# Power.net
KiCad netlist of a schematic drawn in Altium Designer
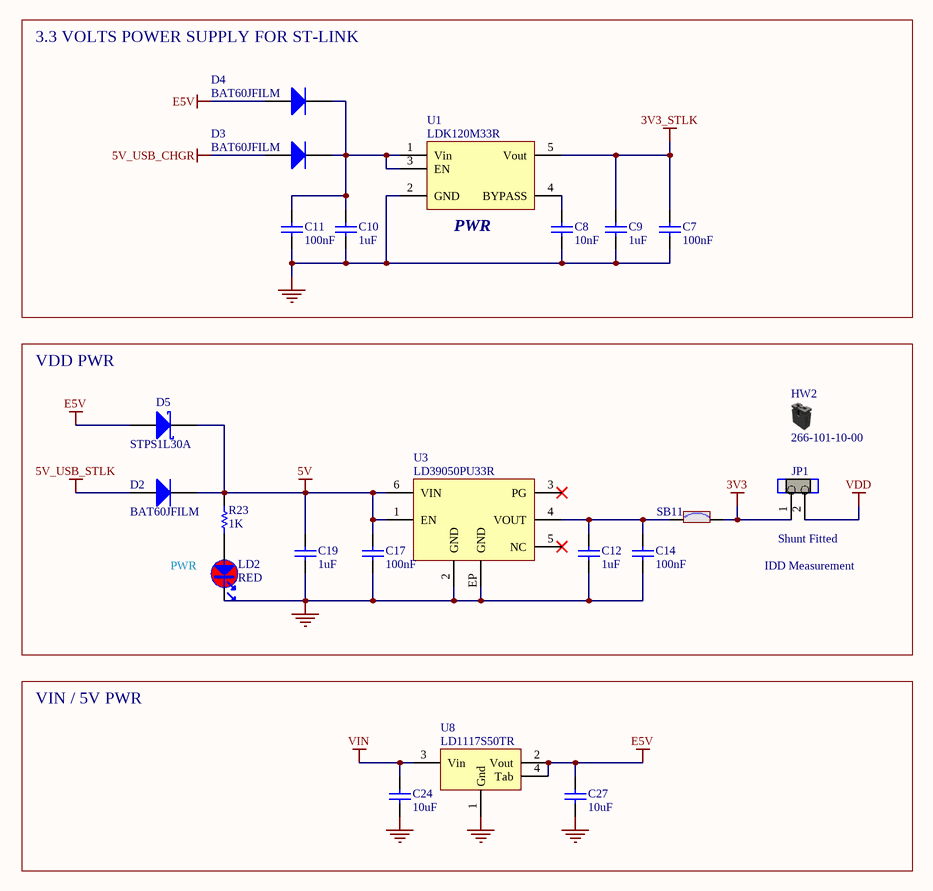
[diagram p0: Power.SchDoc]

(export (version "E")
  (design (tool "Eeschema 10.0.6"))
  (components
    (comp (ref "C7")
      (value "100nF")
      (footprint "C0402")
      (description "Capacitor, MLCC, 100nF, 16V, X7R, 10%, 0402, T=0,5mm")
      (fields
        (field (name "INTERNAL_PART_NUMBER") "MCD-00102")
        (field (name "MANUFACTURER_PART_NUMBER") "CC0402KRX7R7BB104")
        (field (name "PROVIDED_BY") "SUBCO")
      )
      (libsource (lib "MCD_PARTS_database") (part "Capacitor"))
    )
    (comp (ref "C8")
      (value "10nF")
      (footprint "C0402")
      (description "Capacitor, MLCC, 10nF, 16V, X7R, 10%, 0402, T=0.5mm")
      (fields
        (field (name "INTERNAL_PART_NUMBER") "MCD-00011")
        (field (name "MANUFACTURER_PART_NUMBER") "CC0402KRX7R7BB103")
        (field (name "PROVIDED_BY") "SUBCO")
      )
      (libsource (lib "MCD_PARTS_database") (part "Capacitor"))
    )
    (comp (ref "C9")
      (value "1uF")
      (footprint "C0402")
      (description "Capacitor, MLCC, 1uF, 6V3, X5R, 10%, 0402, T=0,5mm")
      (fields
        (field (name "INTERNAL_PART_NUMBER") "MCD-00095")
        (field (name "MANUFACTURER_PART_NUMBER") "GRM155R61E105KA12")
        (field (name "PROVIDED_BY") "SUBCO")
      )
      (libsource (lib "MCD_PARTS_database") (part "Capacitor"))
    )
    (comp (ref "C10")
      (value "1uF")
      (footprint "C0402")
      (description "Capacitor, MLCC, 1uF, 6V3, X5R, 10%, 0402, T=0,5mm")
      (fields
        (field (name "INTERNAL_PART_NUMBER") "MCD-00095")
        (field (name "MANUFACTURER_PART_NUMBER") "GRM155R61E105KA12")
        (field (name "PROVIDED_BY") "SUBCO")
      )
      (libsource (lib "MCD_PARTS_database") (part "Capacitor"))
    )
    (comp (ref "C11")
      (value "100nF")
      (footprint "C0402")
      (description "Capacitor, MLCC, 100nF, 16V, X7R, 10%, 0402, T=0,5mm")
      (fields
        (field (name "INTERNAL_PART_NUMBER") "MCD-00102")
        (field (name "MANUFACTURER_PART_NUMBER") "CC0402KRX7R7BB104")
        (field (name "PROVIDED_BY") "SUBCO")
      )
      (libsource (lib "MCD_PARTS_database") (part "Capacitor"))
    )
    (comp (ref "C12")
      (value "1uF")
      (footprint "C0402")
      (description "Capacitor, MLCC, 1uF, 6V3, X5R, 10%, 0402, T=0,5mm")
      (fields
        (field (name "INTERNAL_PART_NUMBER") "MCD-00095")
        (field (name "MANUFACTURER_PART_NUMBER") "GRM155R61E105KA12")
        (field (name "PROVIDED_BY") "SUBCO")
      )
      (libsource (lib "MCD_PARTS_database") (part "Capacitor"))
    )
    (comp (ref "C14")
      (value "100nF")
      (footprint "C0402")
      (description "Capacitor, MLCC, 100nF, 16V, X7R, 10%, 0402, T=0,5mm")
      (fields
        (field (name "INTERNAL_PART_NUMBER") "MCD-00102")
        (field (name "MANUFACTURER_PART_NUMBER") "CC0402KRX7R7BB104")
        (field (name "PROVIDED_BY") "SUBCO")
      )
      (libsource (lib "MCD_PARTS_database") (part "Capacitor"))
    )
    (comp (ref "C17")
      (value "100nF")
      (footprint "C0402")
      (description "Capacitor, MLCC, 100nF, 16V, X7R, 10%, 0402, T=0,5mm")
      (fields
        (field (name "INTERNAL_PART_NUMBER") "MCD-00102")
        (field (name "MANUFACTURER_PART_NUMBER") "CC0402KRX7R7BB104")
        (field (name "PROVIDED_BY") "SUBCO")
      )
      (libsource (lib "MCD_PARTS_database") (part "Capacitor"))
    )
    (comp (ref "C19")
      (value "1uF")
      (footprint "C0402")
      (description "Capacitor, MLCC, 1uF, 6V3, X5R, 10%, 0402, T=0,5mm")
      (fields
        (field (name "INTERNAL_PART_NUMBER") "MCD-00095")
        (field (name "MANUFACTURER_PART_NUMBER") "GRM155R61E105KA12")
        (field (name "PROVIDED_BY") "SUBCO")
      )
      (libsource (lib "MCD_PARTS_database") (part "Capacitor"))
    )
    (comp (ref "C24")
      (value "10uF")
      (footprint "C0805")
      (description "Capacitor, MLCC, 10uF, 25V, X5R, 10%, 0805, T=0,85mm")
      (fields
        (field (name "INTERNAL_PART_NUMBER") "MCD-00014")
        (field (name "MANUFACTURER_PART_NUMBER") "CC0805KRX5R8BB106")
        (field (name "PROVIDED_BY") "SUBCO")
      )
      (libsource (lib "MCD_PARTS_database") (part "Capacitor"))
    )
    (comp (ref "C27")
      (value "10uF")
      (footprint "C0805")
      (description "Capacitor, MLCC, 10uF, 25V, X5R, 10%, 0805, T=0,85mm")
      (fields
        (field (name "INTERNAL_PART_NUMBER") "MCD-00014")
        (field (name "MANUFACTURER_PART_NUMBER") "CC0805KRX5R8BB106")
        (field (name "PROVIDED_BY") "SUBCO")
      )
      (libsource (lib "MCD_PARTS_database") (part "Capacitor"))
    )
    (comp (ref "D2")
      (value "BAT60JFILM")
      (footprint "DIO_SOD323")
      (fields
        (field (name "INTERNAL_PART_NUMBER") "MCD-00034")
        (field (name "MANUFACTURER") "STMICROELECTRONICS")
        (field (name "BMS_PART_NUMBER") "9151097")
        (field (name "PROVIDED_BY") "SUBCO with ST control")
      )
      (libsource (lib "MCD_PARTS_database") (part "BAT60JFILM"))
    )
    (comp (ref "D3")
      (value "BAT60JFILM")
      (footprint "DIO_SOD323")
      (fields
        (field (name "INTERNAL_PART_NUMBER") "MCD-00034")
        (field (name "MANUFACTURER") "STMICROELECTRONICS")
        (field (name "BMS_PART_NUMBER") "9151097")
        (field (name "PROVIDED_BY") "SUBCO with ST control")
      )
      (libsource (lib "MCD_PARTS_database") (part "BAT60JFILM"))
    )
    (comp (ref "D4")
      (value "BAT60JFILM")
      (footprint "DIO_SOD323")
      (fields
        (field (name "INTERNAL_PART_NUMBER") "MCD-00034")
        (field (name "MANUFACTURER") "STMICROELECTRONICS")
        (field (name "BMS_PART_NUMBER") "9151097")
        (field (name "PROVIDED_BY") "SUBCO with ST control")
      )
      (libsource (lib "MCD_PARTS_database") (part "BAT60JFILM"))
    )
    (comp (ref "D5")
      (value "STPS1L30A")
      (footprint "DIO_SMA_1A_2K")
      (description "LOW DROP POWER SCHOTTKY RECTIFIER 1A 30V VF=0.3V")
      (fields
        (field (name "INTERNAL_PART_NUMBER") "MCD-01059")
        (field (name "MANUFACTURER") "STMICROELECTRONICS")
        (field (name "PROVIDED_BY") "SUBCO with ST control")
      )
      (libsource (lib "MCD_PARTS_database") (part "STPS1L40M"))
    )
    (comp (ref "HW2")
      (value "266-101-10-00")
      (description "SHUNT 1.27mm BLACK")
      (fields
        (field (name "INTERNAL_PART_NUMBER") "MCD-01409")
        (field (name "MANUFACTURER") "W & P Products")
        (field (name "PROVIDED_BY") "SUBCO")
      )
      (libsource (lib "MCD_PARTS_database") (part "Shunt Black 1.27mm 266-101-10-00"))
    )
    (comp (ref "JP1")
      (value "Shunt Fitted")
      (footprint "CON_WP_707-2-02-2-20-00")
      (description "Header, 2x1, 1,27mm, Right Angled, Single Row, Height 3.05mm/1.27mm")
      (fields
        (field (name "INTERNAL_PART_NUMBER") "MCD-01428")
        (field (name "MANUFACTURER_PART_NUMBER") "707-2-02-2-20-00")
        (field (name "PROVIDED_BY") "SUBCO")
      )
      (libsource (lib "MCD_PARTS_database") (part "Jumper_Header1.27 2x1 Fitted"))
    )
    (comp (ref "LD2")
      (value "RED")
      (footprint "LED_0603_RED_H0P4")
      (description "LED, Red, 0603")
      (fields
        (field (name "INTERNAL_PART_NUMBER") "MCD-00322")
        (field (name "MANUFACTURER_PART_NUMBER") "19-217/R6C-AL1M2VY/3T")
        (field (name "PROVIDED_BY") "SUBCO")
      )
      (libsource (lib "MCD_PARTS_database") (part "LED_red"))
    )
    (comp (ref "R23")
      (value "1K")
      (footprint "R0402")
      (description "Resistor,1K,0402,1%,1/16W")
      (fields
        (field (name "INTERNAL_PART_NUMBER") "MCD-00061")
        (field (name "MANUFACTURER_PART_NUMBER") "RC0402FR-071KL")
        (field (name "PROVIDED_BY") "SUBCO")
      )
      (libsource (lib "MCD_PARTS_database") (part "Resistor"))
    )
    (comp (ref "SB11")
      (value "SB_ON")
      (footprint "SOLDER-BRIDGE_R0603-0R")
      (description "Solder Bridge ON")
      (fields
        (field (name "INTERNAL_PART_NUMBER") "MCD-00071")
        (field (name "MANUFACTURER_PART_NUMBER") "RC0603JR-070RL")
        (field (name "PROVIDED_BY") "SUBCO")
      )
      (libsource (lib "MCD_PARTS_database") (part "SB_ON"))
    )
    (comp (ref "U1")
      (value "LDK120M33R")
      (footprint "REG_SOT23-5L")
      (description "200 mA low quiescent current very low noise LDO")
      (fields
        (field (name "INTERNAL_PART_NUMBER") "MCD-00663")
        (field (name "MANUFACTURER") "STMICROELECTRONICS")
        (field (name "PROVIDED_BY") "SUBCO with ST control")
      )
      (libsource (lib "MCD_PARTS_database") (part "LDK120M33R"))
    )
    (comp (ref "U3")
      (value "LD39050PU33R")
      (footprint "ICC_DFN6-EPAD_3X3_P095")
      (description "Low quiescent current and low noise voltage regulators")
      (fields
        (field (name "INTERNAL_PART_NUMBER") "MCD-00215")
        (field (name "MANUFACTURER") "STMICROELECTRONICS")
        (field (name "PROVIDED_BY") "SUBCO with ST control")
      )
      (libsource (lib "MCD_PARTS_database") (part "LD39050PU33R"))
    )
    (comp (ref "U8")
      (value "LD1117S50TR")
      (footprint "REG_SOT223-TAB")
      (description "IC REG LDO 5V 0.8A SOT223")
      (fields
        (field (name "INTERNAL_PART_NUMBER") "MCD-00088")
        (field (name "MANUFACTURER") "STMICROELECTRONICS")
        (field (name "PROVIDED_BY") "SUBCO with ST control")
      )
      (libsource (lib "MCD_PARTS_database") (part "LD1117S50TR"))
    )
  )
  (nets
    (net (code "1") (name "3V3") (class "Default")
      (node (ref "JP1") (pin "1") (pinfunction "1_1") (pintype "passive"))
      (node (ref "SB11") (pin "2") (pinfunction "2_2") (pintype "passive"))
    )
    (net (code "2") (name "3V3_STLK") (class "Default")
      (node (ref "C7") (pin "2") (pinfunction "2_2") (pintype "passive"))
      (node (ref "C9") (pin "2") (pinfunction "2_2") (pintype "passive"))
      (node (ref "U1") (pin "5") (pinfunction "Vout_5") (pintype "power_in"))
    )
    (net (code "3") (name "5V") (class "Default")
      (node (ref "C17") (pin "2") (pinfunction "2_2") (pintype "passive"))
      (node (ref "C19") (pin "2") (pinfunction "2_2") (pintype "passive"))
      (node (ref "D2") (pin "2") (pinfunction "K_2") (pintype "passive"))
      (node (ref "D5") (pin "2") (pinfunction "K_2") (pintype "passive"))
      (node (ref "R23") (pin "2") (pinfunction "2_2") (pintype "passive"))
      (node (ref "U3") (pin "1") (pinfunction "EN_1") (pintype "passive"))
      (node (ref "U3") (pin "6") (pinfunction "VIN_6") (pintype "passive"))
    )
    (net (code "4") (name "5V_USB_CHGR") (class "Default")
      (node (ref "D3") (pin "1") (pinfunction "A_1") (pintype "passive"))
    )
    (net (code "5") (name "5V_USB_STLK") (class "Default")
      (node (ref "D2") (pin "1") (pinfunction "A_1") (pintype "passive"))
    )
    (net (code "6") (name "E5V") (class "Default")
      (node (ref "C27") (pin "2") (pinfunction "2_2") (pintype "passive"))
      (node (ref "D4") (pin "1") (pinfunction "A_1") (pintype "passive"))
      (node (ref "D5") (pin "1") (pinfunction "A_1") (pintype "passive"))
      (node (ref "U8") (pin "2") (pinfunction "Vout_2") (pintype "passive"))
      (node (ref "U8") (pin "4") (pinfunction "Tab_4") (pintype "passive"))
    )
    (net (code "7") (name "GND") (class "Default")
      (node (ref "C10") (pin "1") (pinfunction "1_1") (pintype "passive"))
      (node (ref "C11") (pin "1") (pinfunction "1_1") (pintype "passive"))
      (node (ref "C12") (pin "1") (pinfunction "1_1") (pintype "passive"))
      (node (ref "C14") (pin "1") (pinfunction "1_1") (pintype "passive"))
      (node (ref "C17") (pin "1") (pinfunction "1_1") (pintype "passive"))
      (node (ref "C19") (pin "1") (pinfunction "1_1") (pintype "passive"))
      (node (ref "C24") (pin "1") (pinfunction "1_1") (pintype "passive"))
      (node (ref "C27") (pin "1") (pinfunction "1_1") (pintype "passive"))
      (node (ref "C7") (pin "1") (pinfunction "1_1") (pintype "passive"))
      (node (ref "C8") (pin "1") (pinfunction "1_1") (pintype "passive"))
      (node (ref "C9") (pin "1") (pinfunction "1_1") (pintype "passive"))
      (node (ref "LD2") (pin "2") (pintype "passive"))
      (node (ref "U1") (pin "2") (pinfunction "GND_2") (pintype "passive"))
      (node (ref "U3") (pin "2") (pinfunction "GND_2") (pintype "passive"))
      (node (ref "U3") (pin "EP") (pinfunction "GND_EP") (pintype "passive"))
      (node (ref "U8") (pin "1") (pinfunction "Gnd_1") (pintype "passive"))
    )
    (net (code "8") (name "Net-(D3-K)") (class "Default")
      (node (ref "C10") (pin "2") (pinfunction "2_2") (pintype "passive"))
      (node (ref "C11") (pin "2") (pinfunction "2_2") (pintype "passive"))
      (node (ref "D3") (pin "2") (pinfunction "K_2") (pintype "passive"))
      (node (ref "D4") (pin "2") (pinfunction "K_2") (pintype "passive"))
      (node (ref "U1") (pin "1") (pinfunction "Vin_1") (pintype "power_in"))
      (node (ref "U1") (pin "3") (pinfunction "EN_3") (pintype "passive"))
    )
    (net (code "9") (name "Net-(LD2-Pad1)") (class "Default")
      (node (ref "LD2") (pin "1") (pintype "passive"))
      (node (ref "R23") (pin "1") (pinfunction "1_1") (pintype "passive"))
    )
    (net (code "10") (name "Net-(U1-BYPASS)") (class "Default")
      (node (ref "C8") (pin "2") (pinfunction "2_2") (pintype "passive"))
      (node (ref "U1") (pin "4") (pinfunction "BYPASS_4") (pintype "passive"))
    )
    (net (code "11") (name "Net-(U3-VOUT)") (class "Default")
      (node (ref "C12") (pin "2") (pinfunction "2_2") (pintype "passive"))
      (node (ref "C14") (pin "2") (pinfunction "2_2") (pintype "passive"))
      (node (ref "SB11") (pin "1") (pinfunction "1_1") (pintype "passive"))
      (node (ref "U3") (pin "4") (pinfunction "VOUT_4") (pintype "passive"))
    )
    (net (code "12") (name "VDD") (class "Default")
      (node (ref "JP1") (pin "2") (pinfunction "2_2") (pintype "passive"))
    )
    (net (code "13") (name "VIN") (class "Default")
      (node (ref "C24") (pin "2") (pinfunction "2_2") (pintype "passive"))
      (node (ref "U8") (pin "3") (pinfunction "Vin_3") (pintype "passive"))
    )
    (net (code "14") (name "unconnected-(U3-NC-Pad5)") (class "Default")
      (node (ref "U3") (pin "5") (pinfunction "NC_5") (pintype "passive+no_connect"))
    )
    (net (code "15") (name "unconnected-(U3-PG-Pad3)") (class "Default")
      (node (ref "U3") (pin "3") (pinfunction "PG_3") (pintype "passive+no_connect"))
    )
  )
)
